# solar-radio.net
KiCad netlist of a schematic drawn in EAGLE
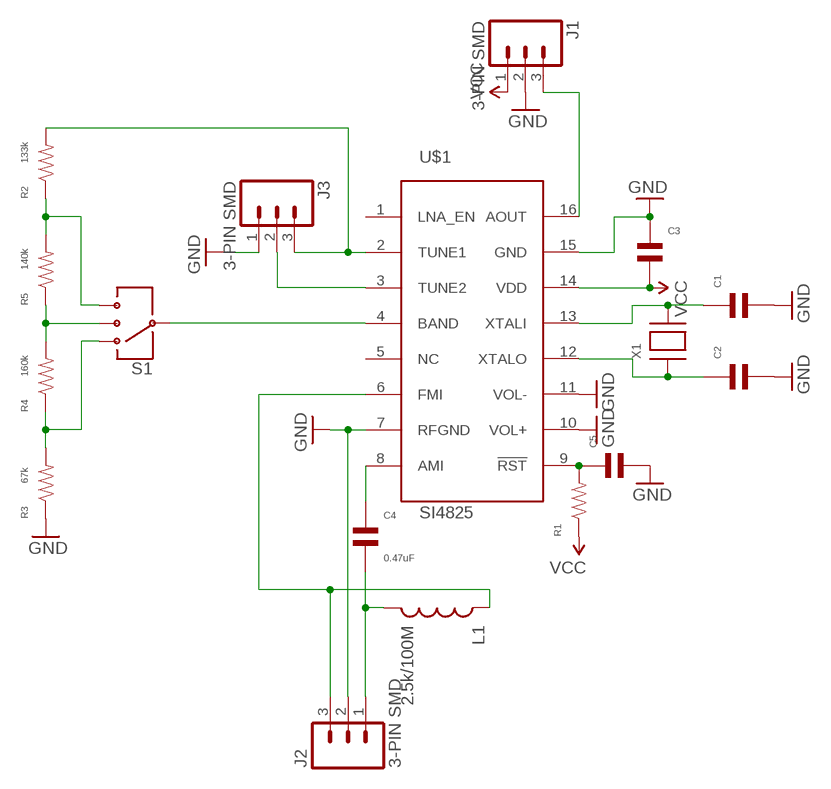
[diagram p0: schematic, sheet 1]

(export (version "E")
  (design (tool "Eeschema 10.0.6"))
  (components
    (comp (ref "C1")
      (value "CAPACITOR_NP_0805")
      (footprint "eagle-import:C0805")
      (libsource (lib "eagle-import") (part "CAPACITOR_NP_0805"))
    )
    (comp (ref "C2")
      (value "CAPACITOR_NP_0805")
      (footprint "eagle-import:C0805")
      (libsource (lib "eagle-import") (part "CAPACITOR_NP_0805"))
    )
    (comp (ref "C3")
      (value "CAPACITOR_NP_0805")
      (footprint "eagle-import:C0805")
      (libsource (lib "eagle-import") (part "CAPACITOR_NP_0805"))
    )
    (comp (ref "C4")
      (value "0.47uF")
      (footprint "eagle-import:C0805")
      (libsource (lib "eagle-import") (part "CAPACITOR_NP_0805"))
    )
    (comp (ref "C5")
      (value "CAPACITOR_NP_0805")
      (footprint "eagle-import:C0805")
      (libsource (lib "eagle-import") (part "CAPACITOR_NP_0805"))
    )
    (comp (ref "J1")
      (value "3-PIN SMD")
      (footprint "eagle-import:JST-3-SMD")
      (libsource (lib "eagle-import") (part "M03JST-SMD"))
    )
    (comp (ref "J2")
      (value "3-PIN SMD")
      (footprint "eagle-import:JST-3-SMD")
      (libsource (lib "eagle-import") (part "M03JST-SMD"))
    )
    (comp (ref "J3")
      (value "3-PIN SMD")
      (footprint "eagle-import:JST-3-SMD")
      (libsource (lib "eagle-import") (part "M03JST-SMD"))
    )
    (comp (ref "L1")
      (value "2.5k/100M")
      (footprint "eagle-import:0805")
      (libsource (lib "eagle-import") (part "INDUCTOR0805"))
    )
    (comp (ref "R1")
      (value "RESISTOR_0805")
      (footprint "eagle-import:R0805")
      (libsource (lib "eagle-import") (part "RESISTOR_0805"))
    )
    (comp (ref "R2")
      (value "133k")
      (footprint "eagle-import:R0805")
      (libsource (lib "eagle-import") (part "RESISTOR_0805"))
    )
    (comp (ref "R3")
      (value "67k")
      (footprint "eagle-import:R0805")
      (libsource (lib "eagle-import") (part "RESISTOR_0805"))
    )
    (comp (ref "R4")
      (value "160k")
      (footprint "eagle-import:R0805")
      (libsource (lib "eagle-import") (part "RESISTOR_0805"))
    )
    (comp (ref "R5")
      (value "140k")
      (footprint "eagle-import:R0805")
      (libsource (lib "eagle-import") (part "RESISTOR_0805"))
    )
    (comp (ref "S1")
      (value "SWITCH-SP3T")
      (footprint "eagle-import:SWITCH-SP3T-SMD")
      (libsource (lib "eagle-import") (part "SWITCH-SP3T"))
    )
    (comp (ref "U$1")
      (value "SI4825")
      (footprint "eagle-import:SOIC16N")
      (libsource (lib "eagle-import") (part "SI4825"))
    )
    (comp (ref "X1")
      (value "XTAL-3.2X1.5")
      (footprint "eagle-import:XTAL3215")
      (libsource (lib "eagle-import") (part "XTAL-3.2X1.5"))
    )
  )
  (nets
    (net (code "1") (name "GND") (class "Default")
      (node (ref "C1") (pin "P$2") (pinfunction "P$2_P$2") (pintype "passive"))
      (node (ref "C2") (pin "P$2") (pinfunction "P$2_P$2") (pintype "passive"))
      (node (ref "C3") (pin "P$1") (pinfunction "P$1_P$1") (pintype "passive"))
      (node (ref "C5") (pin "P$2") (pinfunction "P$2_P$2") (pintype "passive"))
      (node (ref "J1") (pin "2") (pinfunction "2_2") (pintype "passive"))
      (node (ref "J2") (pin "2") (pinfunction "2_2") (pintype "passive"))
      (node (ref "J3") (pin "1") (pinfunction "1_1") (pintype "passive"))
      (node (ref "R3") (pin "P$1") (pinfunction "P$1_P$1") (pintype "passive"))
      (node (ref "U$1") (pin "10") (pinfunction "VOL+_10") (pintype "bidirectional"))
      (node (ref "U$1") (pin "11") (pinfunction "VOL-_11") (pintype "bidirectional"))
      (node (ref "U$1") (pin "15") (pinfunction "GND_15") (pintype "bidirectional"))
      (node (ref "U$1") (pin "7") (pinfunction "RFGND_7") (pintype "bidirectional"))
    )
    (net (code "2") (name "Net-(C4-PadP$2)") (class "Default")
      (node (ref "C4") (pin "P$2") (pinfunction "P$2_P$2") (pintype "passive"))
      (node (ref "J2") (pin "1") (pinfunction "1_1") (pintype "passive"))
      (node (ref "L1") (pin "2") (pinfunction "2_2") (pintype "passive"))
    )
    (net (code "3") (name "Net-(R2-PadP$1)") (class "Default")
      (node (ref "R2") (pin "P$1") (pinfunction "P$1_P$1") (pintype "passive"))
      (node (ref "R5") (pin "P$2") (pinfunction "P$2_P$2") (pintype "passive"))
      (node (ref "S1") (pin "4") (pinfunction "4_4") (pintype "bidirectional"))
    )
    (net (code "4") (name "Net-(R3-PadP$2)") (class "Default")
      (node (ref "R3") (pin "P$2") (pinfunction "P$2_P$2") (pintype "passive"))
      (node (ref "R4") (pin "P$1") (pinfunction "P$1_P$1") (pintype "passive"))
      (node (ref "S1") (pin "1") (pinfunction "1_1") (pintype "bidirectional"))
    )
    (net (code "5") (name "Net-(R4-PadP$2)") (class "Default")
      (node (ref "R4") (pin "P$2") (pinfunction "P$2_P$2") (pintype "passive"))
      (node (ref "R5") (pin "P$1") (pinfunction "P$1_P$1") (pintype "passive"))
      (node (ref "S1") (pin "2") (pinfunction "2_2") (pintype "bidirectional"))
    )
    (net (code "6") (name "Net-(U$1-AMI)") (class "Default")
      (node (ref "C4") (pin "P$1") (pinfunction "P$1_P$1") (pintype "passive"))
      (node (ref "U$1") (pin "8") (pinfunction "AMI_8") (pintype "bidirectional"))
    )
    (net (code "7") (name "Net-(U$1-AOUT)") (class "Default")
      (node (ref "J1") (pin "3") (pinfunction "3_3") (pintype "passive"))
      (node (ref "U$1") (pin "16") (pinfunction "AOUT_16") (pintype "bidirectional"))
    )
    (net (code "8") (name "Net-(U$1-BAND)") (class "Default")
      (node (ref "S1") (pin "3") (pinfunction "3_3") (pintype "bidirectional"))
      (node (ref "U$1") (pin "4") (pinfunction "BAND_4") (pintype "bidirectional"))
    )
    (net (code "9") (name "Net-(U$1-FMI)") (class "Default")
      (node (ref "J2") (pin "3") (pinfunction "3_3") (pintype "passive"))
      (node (ref "L1") (pin "1") (pinfunction "1_1") (pintype "passive"))
      (node (ref "U$1") (pin "6") (pinfunction "FMI_6") (pintype "bidirectional"))
    )
    (net (code "10") (name "Net-(U$1-TUNE1)") (class "Default")
      (node (ref "J3") (pin "3") (pinfunction "3_3") (pintype "passive"))
      (node (ref "R2") (pin "P$2") (pinfunction "P$2_P$2") (pintype "passive"))
      (node (ref "U$1") (pin "2") (pinfunction "TUNE1_2") (pintype "bidirectional"))
    )
    (net (code "11") (name "Net-(U$1-TUNE2)") (class "Default")
      (node (ref "J3") (pin "2") (pinfunction "2_2") (pintype "passive"))
      (node (ref "U$1") (pin "3") (pinfunction "TUNE2_3") (pintype "bidirectional"))
    )
    (net (code "12") (name "Net-(U$1-XTALI)") (class "Default")
      (node (ref "C1") (pin "P$1") (pinfunction "P$1_P$1") (pintype "passive"))
      (node (ref "U$1") (pin "13") (pinfunction "XTALI_13") (pintype "bidirectional"))
      (node (ref "X1") (pin "P$2") (pinfunction "P$2_P$2") (pintype "bidirectional"))
    )
    (net (code "13") (name "Net-(U$1-XTALO)") (class "Default")
      (node (ref "C2") (pin "P$1") (pinfunction "P$1_P$1") (pintype "passive"))
      (node (ref "U$1") (pin "12") (pinfunction "XTALO_12") (pintype "bidirectional"))
      (node (ref "X1") (pin "P$1") (pinfunction "P$1_P$1") (pintype "bidirectional"))
    )
    (net (code "14") (name "Net-(U$1-~{RST})") (class "Default")
      (node (ref "C5") (pin "P$1") (pinfunction "P$1_P$1") (pintype "passive"))
      (node (ref "R1") (pin "P$2") (pinfunction "P$2_P$2") (pintype "passive"))
      (node (ref "U$1") (pin "9") (pinfunction "~{RST}_9") (pintype "bidirectional"))
    )
    (net (code "15") (name "VCC") (class "Default")
      (node (ref "C3") (pin "P$2") (pinfunction "P$2_P$2") (pintype "passive"))
      (node (ref "J1") (pin "1") (pinfunction "1_1") (pintype "passive"))
      (node (ref "R1") (pin "P$1") (pinfunction "P$1_P$1") (pintype "passive"))
      (node (ref "U$1") (pin "14") (pinfunction "VDD_14") (pintype "bidirectional"))
    )
    (net (code "16") (name "unconnected-(U$1-LNA_EN-Pad1)") (class "Default")
      (node (ref "U$1") (pin "1") (pinfunction "LNA_EN_1") (pintype "bidirectional"))
    )
    (net (code "17") (name "unconnected-(U$1-NC-Pad5)") (class "Default")
      (node (ref "U$1") (pin "5") (pinfunction "NC_5") (pintype "bidirectional"))
    )
  )
)
